# SNAC_7ch_SNES_in_Housing_-_Compact.net
KiCad netlist of a schematic drawn in EAGLE
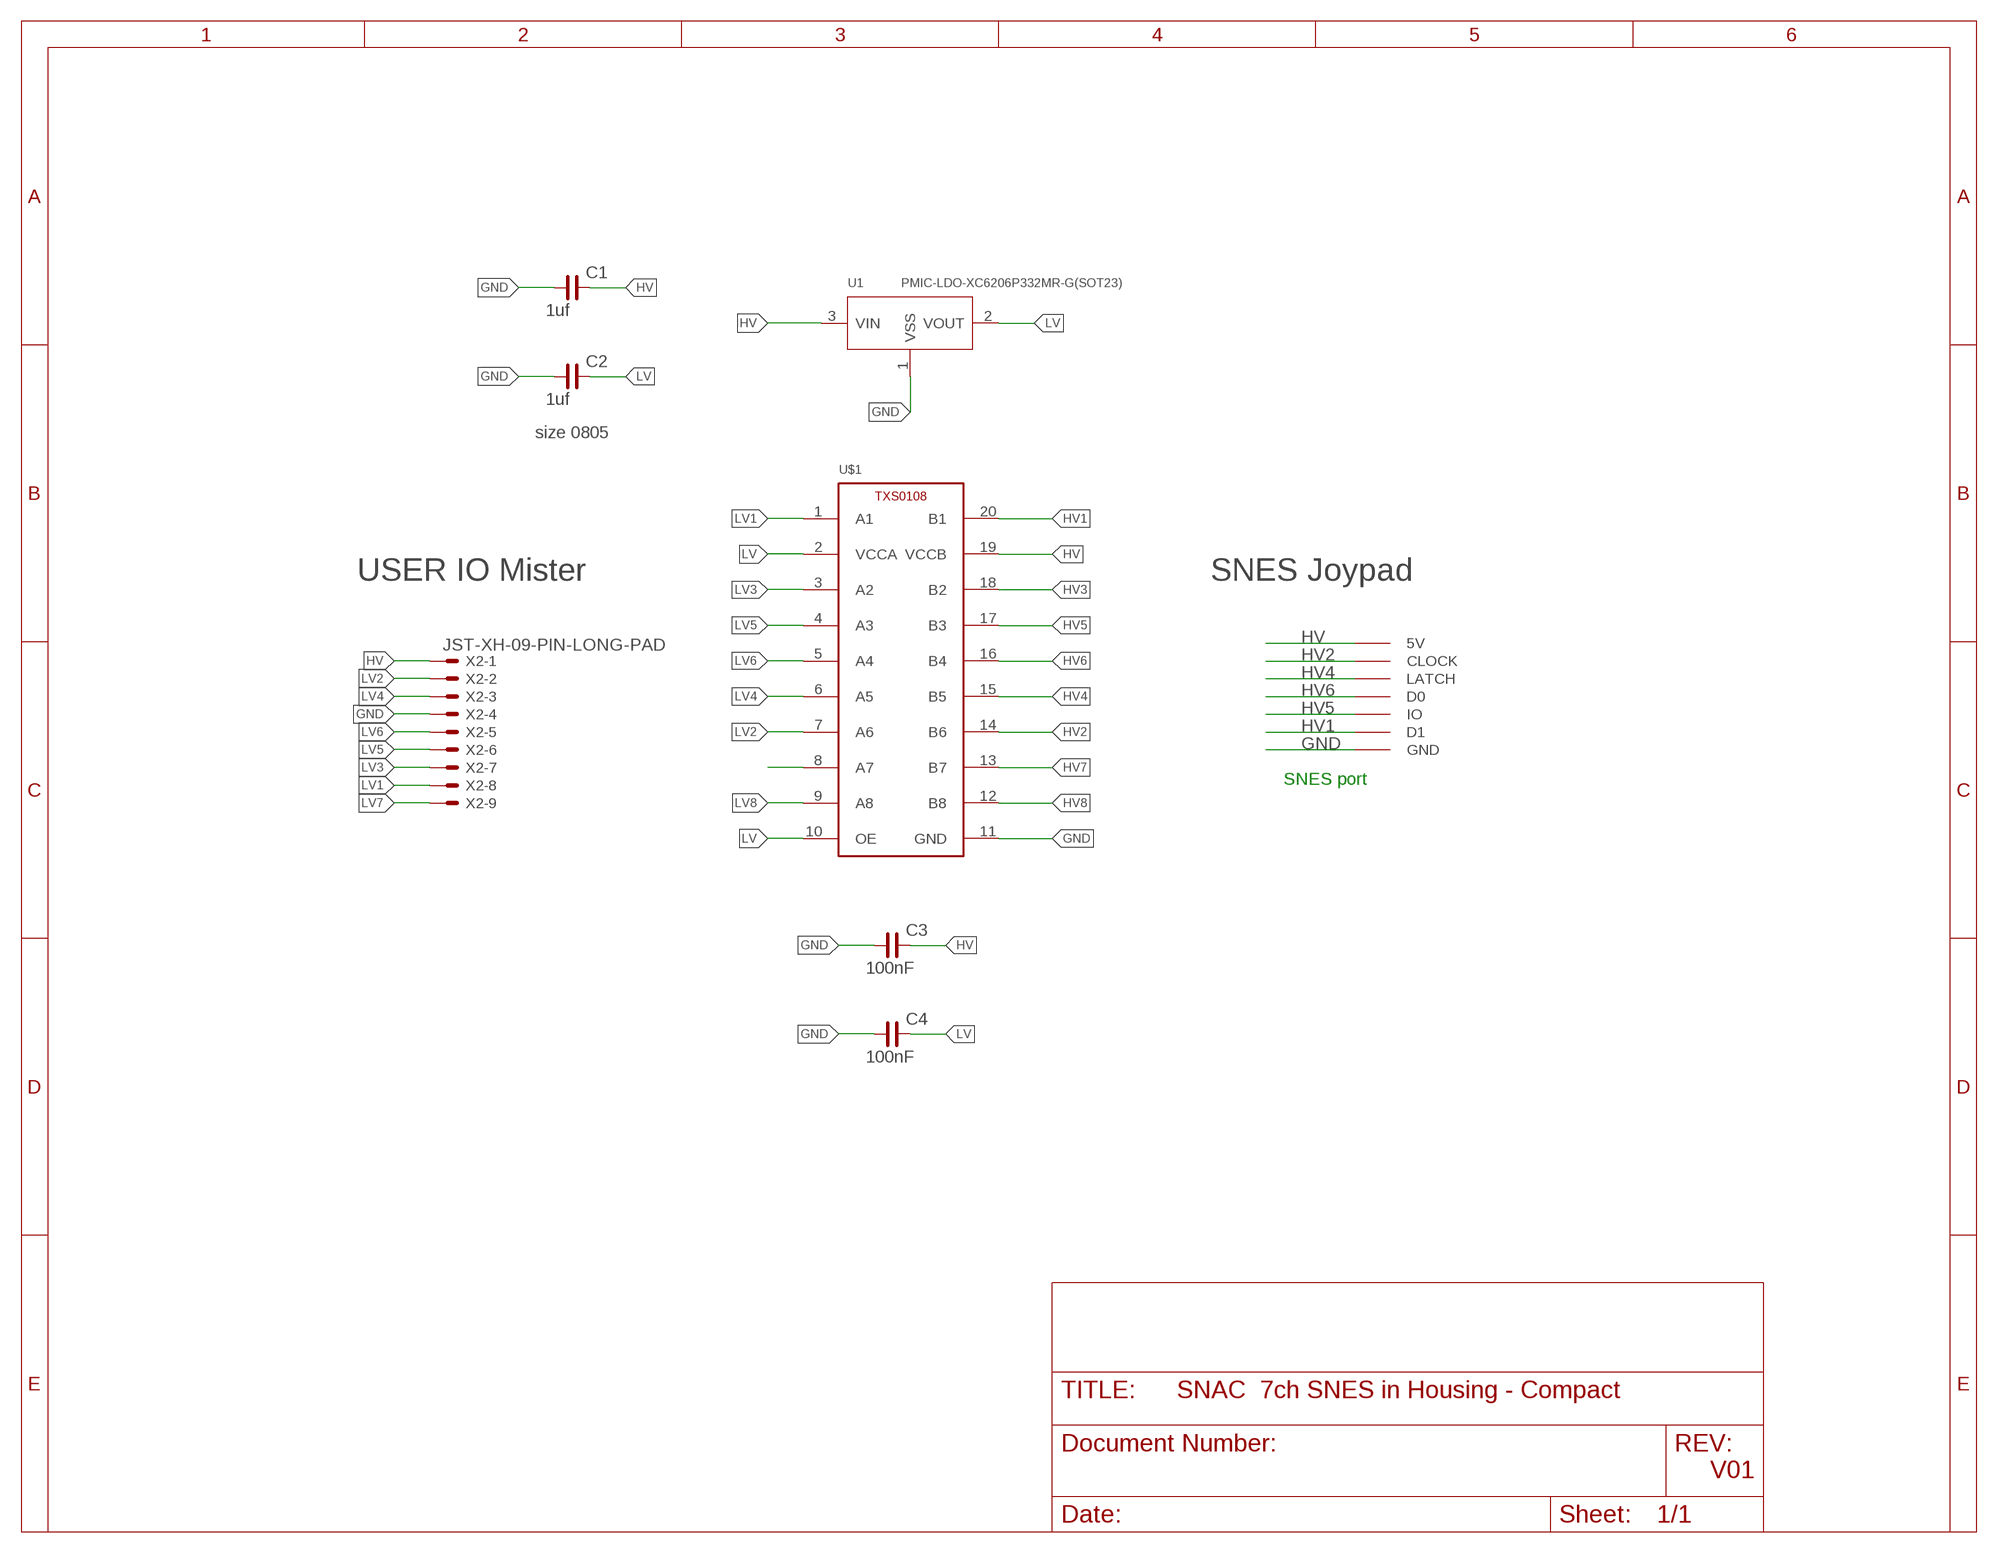
[diagram p0: schematic, sheet 1]

(export (version "E")
  (design (tool "Eeschema 10.0.6"))
  (components
    (comp (ref "C1")
      (value "1uf")
      (footprint "eagle-import:C0805")
      (libsource (lib "eagle-import") (part "C_0805"))
    )
    (comp (ref "C2")
      (value "1uf")
      (footprint "eagle-import:C0805")
      (libsource (lib "eagle-import") (part "C_0805"))
    )
    (comp (ref "C3")
      (value "100nF")
      (footprint "eagle-import:C0805")
      (libsource (lib "eagle-import") (part "C_0805"))
    )
    (comp (ref "C4")
      (value "100nF")
      (footprint "eagle-import:C0805")
      (libsource (lib "eagle-import") (part "C_0805"))
    )
    (comp (ref "U$1")
      (value "TXS0108")
      (footprint "eagle-import:R-PUSON-N20")
      (libsource (lib "eagle-import") (part "TXS0108"))
    )
    (comp (ref "U$3")
      (value "SNESCONN")
      (footprint "eagle-import:SNESCONN")
      (libsource (lib "eagle-import") (part "SNESCONN"))
    )
    (comp (ref "U1")
      (value "PMIC-LDO-XC6206P332MR-G(SOT23)")
      (footprint "eagle-import:SOT-23")
      (fields (field (name "MF") "Torex") (field (name "MP") "XC6206P332MR-G"))
      (libsource (lib "eagle-import") (part "PMIC-LDO-XC6206P332MR-G(SOT23)"))
    )
    (comp (ref "X2")
      (value "JST-XH-09-PIN-LONG-PAD")
      (footprint "eagle-import:JST-XH-09-PACKAGE-LONG-PAD")
      (libsource (lib "eagle-import") (part "JST-XH-09-PIN-LONG-PAD"))
    )
  )
  (nets
    (net (code "1") (name "GND") (class "Default")
      (node (ref "C1") (pin "1") (pinfunction "1_1") (pintype "passive"))
      (node (ref "C2") (pin "1") (pinfunction "1_1") (pintype "passive"))
      (node (ref "C3") (pin "1") (pinfunction "1_1") (pintype "passive"))
      (node (ref "C4") (pin "1") (pinfunction "1_1") (pintype "passive"))
      (node (ref "U$1") (pin "11") (pinfunction "GND_11") (pintype "bidirectional"))
      (node (ref "U$3") (pin "GND") (pinfunction "GND_GND") (pintype "power_in"))
      (node (ref "U1") (pin "1") (pinfunction "VSS_1") (pintype "power_in"))
      (node (ref "X2") (pin "4") (pinfunction "S_4") (pintype "passive"))
    )
    (net (code "2") (name "HV") (class "Default")
      (node (ref "C1") (pin "2") (pinfunction "2_2") (pintype "passive"))
      (node (ref "C3") (pin "2") (pinfunction "2_2") (pintype "passive"))
      (node (ref "U$1") (pin "19") (pinfunction "VCCB_19") (pintype "bidirectional"))
      (node (ref "U$3") (pin "5V") (pinfunction "5V_5V") (pintype "input"))
      (node (ref "U1") (pin "3") (pinfunction "VIN_3") (pintype "input"))
      (node (ref "X2") (pin "1") (pinfunction "S_1") (pintype "passive"))
    )
    (net (code "3") (name "HV1") (class "Default")
      (node (ref "U$1") (pin "20") (pinfunction "B1_20") (pintype "bidirectional"))
      (node (ref "U$3") (pin "D1") (pinfunction "D1_D1") (pintype "bidirectional"))
    )
    (net (code "4") (name "HV2") (class "Default")
      (node (ref "U$1") (pin "14") (pinfunction "B6_14") (pintype "bidirectional"))
      (node (ref "U$3") (pin "CLOCK") (pinfunction "CLOCK_CLOCK") (pintype "input"))
    )
    (net (code "5") (name "HV3") (class "Default")
      (node (ref "U$1") (pin "18") (pinfunction "B2_18") (pintype "bidirectional"))
    )
    (net (code "6") (name "HV4") (class "Default")
      (node (ref "U$1") (pin "15") (pinfunction "B5_15") (pintype "bidirectional"))
      (node (ref "U$3") (pin "LATCH") (pinfunction "LATCH_LATCH") (pintype "input"))
    )
    (net (code "7") (name "HV5") (class "Default")
      (node (ref "U$1") (pin "17") (pinfunction "B3_17") (pintype "bidirectional"))
      (node (ref "U$3") (pin "IO") (pinfunction "IO_IO") (pintype "bidirectional"))
    )
    (net (code "8") (name "HV6") (class "Default")
      (node (ref "U$1") (pin "16") (pinfunction "B4_16") (pintype "bidirectional"))
      (node (ref "U$3") (pin "D0") (pinfunction "D0_D0") (pintype "bidirectional"))
    )
    (net (code "9") (name "HV7") (class "Default")
      (node (ref "U$1") (pin "13") (pinfunction "B7_13") (pintype "bidirectional"))
    )
    (net (code "10") (name "HV8") (class "Default")
      (node (ref "U$1") (pin "12") (pinfunction "B8_12") (pintype "bidirectional"))
    )
    (net (code "11") (name "LV") (class "Default")
      (node (ref "C2") (pin "2") (pinfunction "2_2") (pintype "passive"))
      (node (ref "C4") (pin "2") (pinfunction "2_2") (pintype "passive"))
      (node (ref "U$1") (pin "10") (pinfunction "OE_10") (pintype "bidirectional"))
      (node (ref "U$1") (pin "2") (pinfunction "VCCA_2") (pintype "bidirectional"))
      (node (ref "U1") (pin "2") (pinfunction "VOUT_2") (pintype "output"))
    )
    (net (code "12") (name "LV1") (class "Default")
      (node (ref "U$1") (pin "1") (pinfunction "A1_1") (pintype "bidirectional"))
      (node (ref "X2") (pin "8") (pinfunction "S_8") (pintype "passive"))
    )
    (net (code "13") (name "LV2") (class "Default")
      (node (ref "U$1") (pin "7") (pinfunction "A6_7") (pintype "bidirectional"))
      (node (ref "X2") (pin "2") (pinfunction "S_2") (pintype "passive"))
    )
    (net (code "14") (name "LV3") (class "Default")
      (node (ref "U$1") (pin "3") (pinfunction "A2_3") (pintype "bidirectional"))
      (node (ref "X2") (pin "7") (pinfunction "S_7") (pintype "passive"))
    )
    (net (code "15") (name "LV4") (class "Default")
      (node (ref "U$1") (pin "6") (pinfunction "A5_6") (pintype "bidirectional"))
      (node (ref "X2") (pin "3") (pinfunction "S_3") (pintype "passive"))
    )
    (net (code "16") (name "LV5") (class "Default")
      (node (ref "U$1") (pin "4") (pinfunction "A3_4") (pintype "bidirectional"))
      (node (ref "X2") (pin "6") (pinfunction "S_6") (pintype "passive"))
    )
    (net (code "17") (name "LV6") (class "Default")
      (node (ref "U$1") (pin "5") (pinfunction "A4_5") (pintype "bidirectional"))
      (node (ref "X2") (pin "5") (pinfunction "S_5") (pintype "passive"))
    )
    (net (code "18") (name "LV7") (class "Default")
      (node (ref "X2") (pin "9") (pinfunction "S_9") (pintype "passive"))
    )
    (net (code "19") (name "LV8") (class "Default")
      (node (ref "U$1") (pin "9") (pinfunction "A8_9") (pintype "bidirectional"))
    )
    (net (code "20") (name "unconnected-(U$1-A7-Pad8)") (class "Default")
      (node (ref "U$1") (pin "8") (pinfunction "A7_8") (pintype "bidirectional"))
    )
  )
)
